# PROIECT.net
KiCad netlist of a schematic drawn in EAGLE
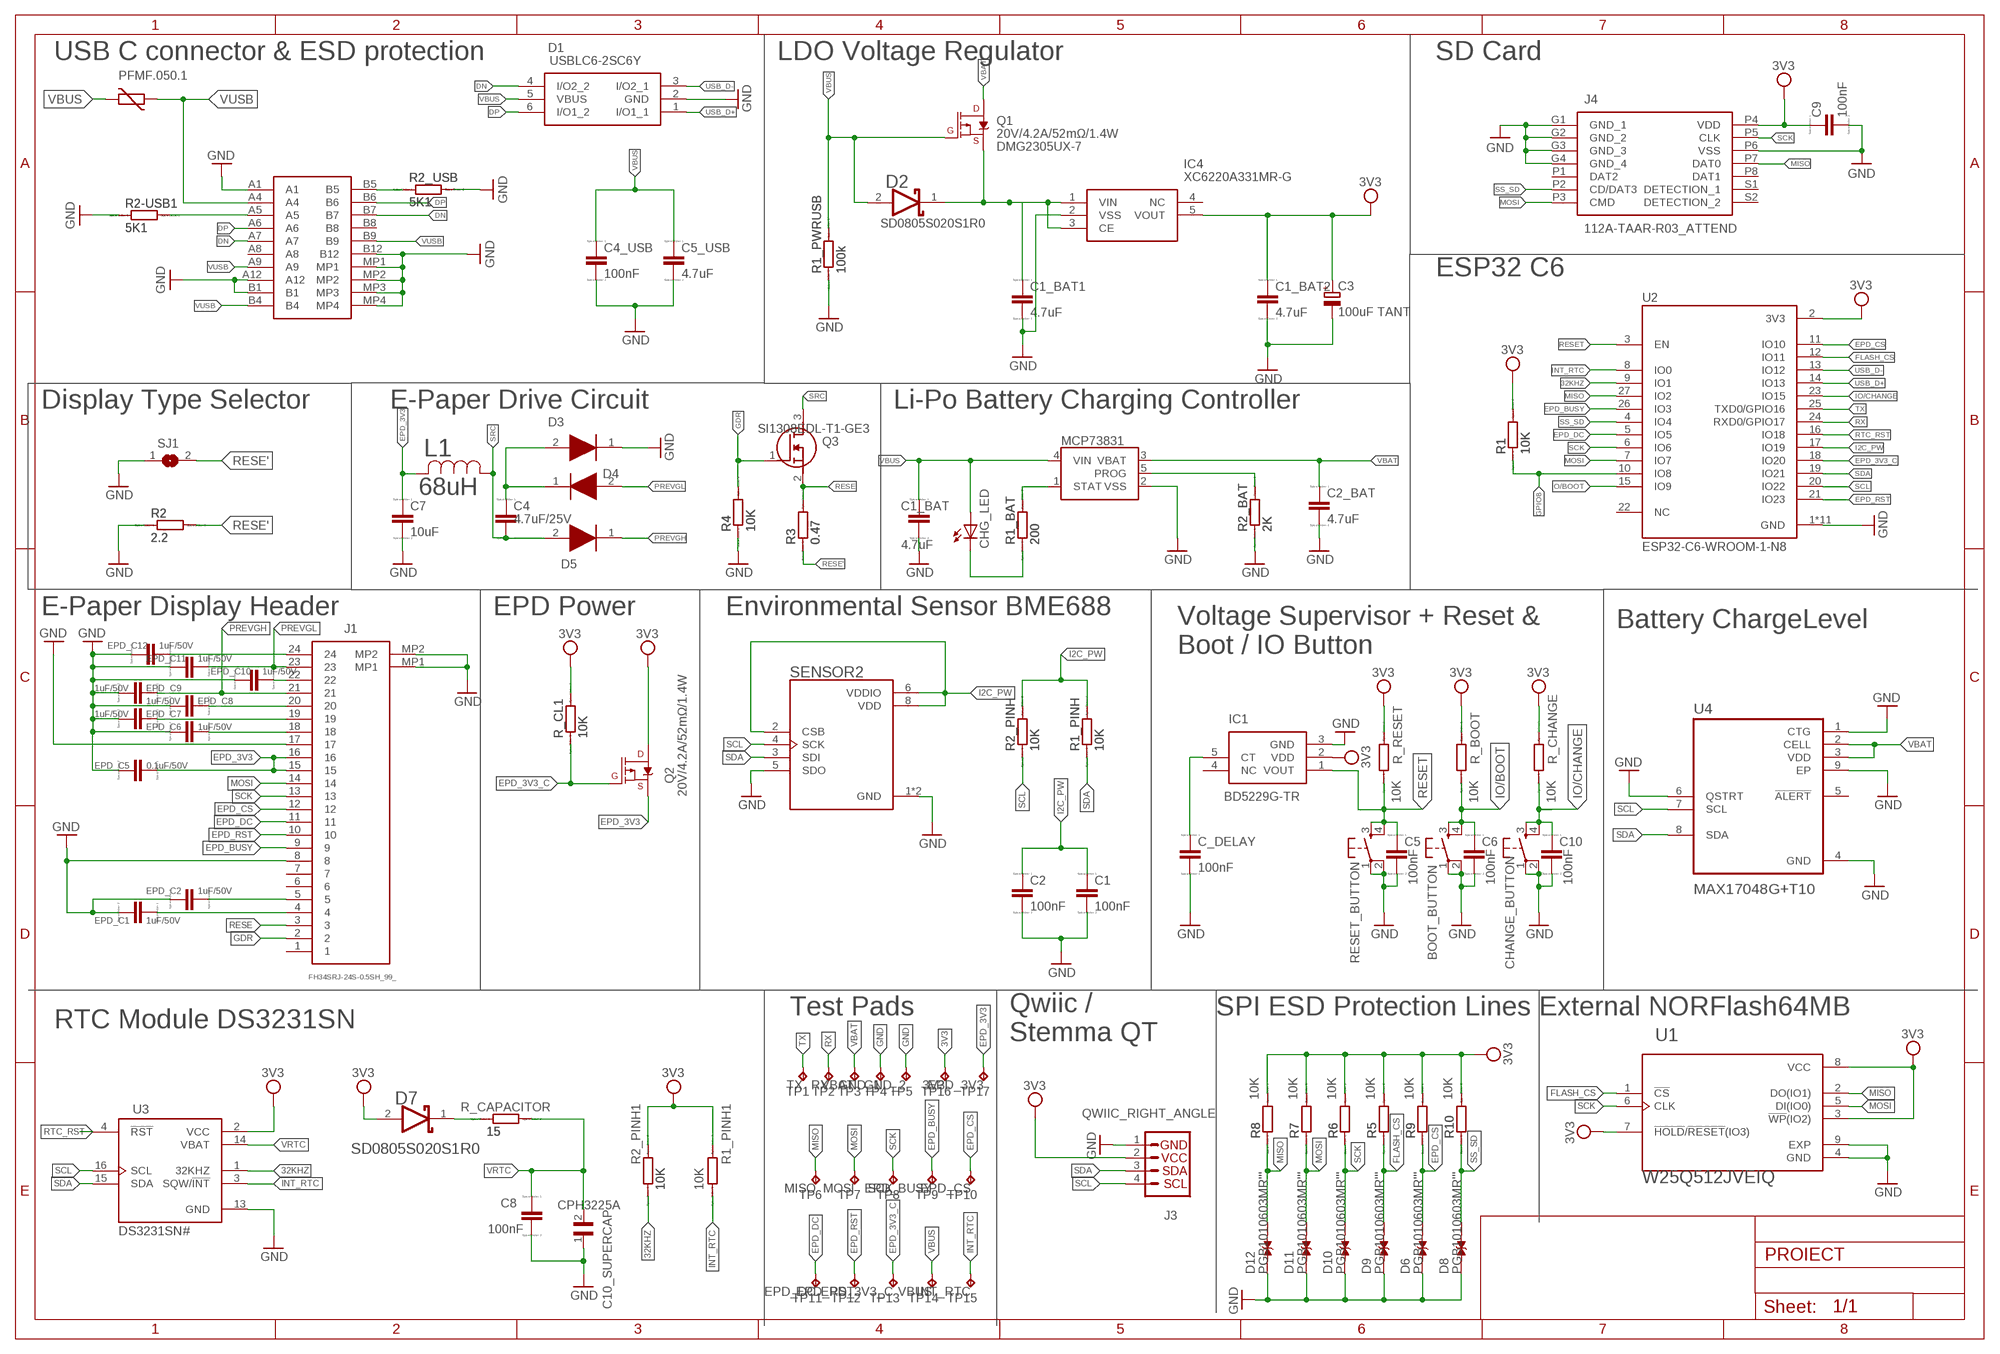
[diagram p0: schematic, sheet 1]

(export (version "E")
  (design (tool "Eeschema 10.0.6"))
  (components
    (comp (ref "BOOT_BUTTON")
      (value "BUTTON_CUSYOMV1")
      (footprint "eagle-import:MYBUTTON")
      (libsource (lib "eagle-import") (part "BUTTON_CUSYOMV1"))
    )
    (comp (ref "C1")
      (value "100nF")
      (footprint "eagle-import:ESP32_WROVER_EAGLE-LTSPICE_C0402")
      (libsource (lib "eagle-import") (part "ESP32_WROVER_EAGLE-LTSPICE_C"))
    )
    (comp (ref "C1_BAT")
      (value "4.7uF")
      (footprint "eagle-import:EAGLE-LTSPICE_C0402")
      (libsource (lib "eagle-import") (part "EAGLE-LTSPICE_CC0402"))
    )
    (comp (ref "C1_BAT1")
      (value "4.7uF")
      (footprint "eagle-import:ESP32_WROVER_EAGLE-LTSPICE_C0402")
      (libsource (lib "eagle-import") (part "ESP32_WROVER_EAGLE-LTSPICE_C"))
    )
    (comp (ref "C1_BAT2")
      (value "4.7uF")
      (footprint "eagle-import:ESP32_WROVER_EAGLE-LTSPICE_C0402")
      (libsource (lib "eagle-import") (part "ESP32_WROVER_EAGLE-LTSPICE_C"))
    )
    (comp (ref "C2")
      (value "100nF")
      (footprint "eagle-import:ESP32_WROVER_EAGLE-LTSPICE_C0402")
      (libsource (lib "eagle-import") (part "ESP32_WROVER_EAGLE-LTSPICE_C"))
    )
    (comp (ref "C2_BAT")
      (value "4.7uF")
      (footprint "eagle-import:EAGLE-LTSPICE_C0402")
      (libsource (lib "eagle-import") (part "EAGLE-LTSPICE_CC0402"))
    )
    (comp (ref "C3")
      (value "100uF TANT")
      (footprint "eagle-import:RCL_CT3528")
      (libsource (lib "eagle-import") (part "RCL_CPOL-EUCT3528"))
    )
    (comp (ref "C4")
      (value "4.7uF/25V")
      (footprint "eagle-import:EAGLE-LTSPICE_C0402")
      (libsource (lib "eagle-import") (part "EAGLE-LTSPICE_CC0402"))
    )
    (comp (ref "C4_USB")
      (value "100nF")
      (footprint "eagle-import:ESP32_WROVER_EAGLE-LTSPICE_C0402")
      (libsource (lib "eagle-import") (part "ESP32_WROVER_EAGLE-LTSPICE_C"))
    )
    (comp (ref "C5")
      (value "100nF")
      (footprint "eagle-import:EAGLE-LTSPICE_C0402")
      (libsource (lib "eagle-import") (part "EAGLE-LTSPICE_CC0402"))
    )
    (comp (ref "C5_USB")
      (value "4.7uF")
      (footprint "eagle-import:ESP32_WROVER_EAGLE-LTSPICE_C0402")
      (libsource (lib "eagle-import") (part "ESP32_WROVER_EAGLE-LTSPICE_C"))
    )
    (comp (ref "C6")
      (value "100nF")
      (footprint "eagle-import:EAGLE-LTSPICE_C0402")
      (libsource (lib "eagle-import") (part "EAGLE-LTSPICE_CC0402"))
    )
    (comp (ref "C7")
      (value "10uF")
      (footprint "eagle-import:EAGLE-LTSPICE_C0402")
      (libsource (lib "eagle-import") (part "EAGLE-LTSPICE_CC0402"))
    )
    (comp (ref "C8")
      (value "100nF")
      (footprint "eagle-import:EAGLE-LTSPICE_C0402")
      (libsource (lib "eagle-import") (part "EAGLE-LTSPICE_CC0402"))
    )
    (comp (ref "C9")
      (value "100nF")
      (footprint "eagle-import:EAGLE-LTSPICE_C0402")
      (libsource (lib "eagle-import") (part "EAGLE-LTSPICE_CC0402"))
    )
    (comp (ref "C10")
      (value "100nF")
      (footprint "eagle-import:EAGLE-LTSPICE_C0402")
      (libsource (lib "eagle-import") (part "EAGLE-LTSPICE_CC0402"))
    )
    (comp (ref "C10_SUPERCAP")
      (value "CPH3225A")
      (footprint "eagle-import:CAPCP3225X100N")
      (fields (field (name "MF") "Seiko Instruments"))
      (libsource (lib "eagle-import") (part "CPH3225A"))
    )
    (comp (ref "CHANGE_BUTTON")
      (value "BUTTON_CUSYOMV1")
      (footprint "eagle-import:MYBUTTON")
      (libsource (lib "eagle-import") (part "BUTTON_CUSYOMV1"))
    )
    (comp (ref "CHG_LED")
      (value "ADAFRUIT_LEDCHIP-LED0603")
      (footprint "eagle-import:ADAFRUIT_CHIP-LED0603")
      (libsource (lib "eagle-import") (part "ADAFRUIT_LEDCHIP-LED0603"))
    )
    (comp (ref "C_DELAY")
      (value "100nF")
      (footprint "eagle-import:EAGLE-LTSPICE_C0402")
      (libsource (lib "eagle-import") (part "EAGLE-LTSPICE_CC0402"))
    )
    (comp (ref "D1")
      (value "USBLC6-2SC6Y")
      (footprint "eagle-import:SOT95P280X145-6N")
      (fields (field (name "MF") "STMicroelectronics"))
      (libsource (lib "eagle-import") (part "USBLC6-2SC6Y"))
    )
    (comp (ref "D2")
      (value "ESP32_WROVER_AVX---SD0805S020S1R0_AVX_SD0805S020S1R0_0_0AVX_SD0805S020S1R0_0_0")
      (footprint "eagle-import:ESP32_WROVER_AVX---SD0805S020S1R0_AVX_SD0805S020S1R0_0")
      (fields
        (field (name "DIGIKEY_PART_NUMBER") "478-7800-1-ND")
        (field (name "MF") "AVX")
        (field (name "MOUSER_PART_NUMBER") "581-SD0805S020S1R0")
      )
      (libsource (lib "eagle-import") (part "ESP32_WROVER_AVX---SD0805S020S1R0_AVX_SD0805S020S1R0_0_0AVX_SD0805S020S1R0_0_0"))
    )
    (comp (ref "D3")
      (value "MBR0530'''")
      (footprint "eagle-import:SOD3716X135N")
      (libsource (lib "eagle-import") (part "MBR0530'''"))
    )
    (comp (ref "D4")
      (value "MBR0530'''")
      (footprint "eagle-import:SOD3716X135N")
      (libsource (lib "eagle-import") (part "MBR0530'''"))
    )
    (comp (ref "D5")
      (value "MBR0530'''")
      (footprint "eagle-import:SOD3716X135N")
      (libsource (lib "eagle-import") (part "MBR0530'''"))
    )
    (comp (ref "D6")
      (value "PGB1010603MR'''")
      (footprint "eagle-import:DIOC1608X36N")
      (libsource (lib "eagle-import") (part "PGB1010603MR'''"))
    )
    (comp (ref "D7")
      (value "ESP32_WROVER_AVX---SD0805S020S1R0_AVX_SD0805S020S1R0_0_0AVX_SD0805S020S1R0_0_0")
      (footprint "eagle-import:ESP32_WROVER_AVX---SD0805S020S1R0_AVX_SD0805S020S1R0_0")
      (fields
        (field (name "DIGIKEY_PART_NUMBER") "478-7800-1-ND")
        (field (name "MF") "AVX")
        (field (name "MOUSER_PART_NUMBER") "581-SD0805S020S1R0")
      )
      (libsource (lib "eagle-import") (part "ESP32_WROVER_AVX---SD0805S020S1R0_AVX_SD0805S020S1R0_0_0AVX_SD0805S020S1R0_0_0"))
    )
    (comp (ref "D8")
      (value "PGB1010603MR'''")
      (footprint "eagle-import:DIOC1608X36N")
      (libsource (lib "eagle-import") (part "PGB1010603MR'''"))
    )
    (comp (ref "D9")
      (value "PGB1010603MR'''")
      (footprint "eagle-import:DIOC1608X36N")
      (libsource (lib "eagle-import") (part "PGB1010603MR'''"))
    )
    (comp (ref "D10")
      (value "PGB1010603MR'''")
      (footprint "eagle-import:DIOC1608X36N")
      (libsource (lib "eagle-import") (part "PGB1010603MR'''"))
    )
    (comp (ref "D11")
      (value "PGB1010603MR'''")
      (footprint "eagle-import:DIOC1608X36N")
      (libsource (lib "eagle-import") (part "PGB1010603MR'''"))
    )
    (comp (ref "D12")
      (value "PGB1010603MR'''")
      (footprint "eagle-import:DIOC1608X36N")
      (libsource (lib "eagle-import") (part "PGB1010603MR'''"))
    )
    (comp (ref "EPD_C1")
      (value "1uF/50V")
      (footprint "eagle-import:EAGLE-LTSPICE_C0402")
      (libsource (lib "eagle-import") (part "EAGLE-LTSPICE_CC0402"))
    )
    (comp (ref "EPD_C2")
      (value "1uF/50V")
      (footprint "eagle-import:EAGLE-LTSPICE_C0402")
      (libsource (lib "eagle-import") (part "EAGLE-LTSPICE_CC0402"))
    )
    (comp (ref "EPD_C5")
      (value "0.1uF/50V")
      (footprint "eagle-import:EAGLE-LTSPICE_C0402")
      (libsource (lib "eagle-import") (part "EAGLE-LTSPICE_CC0402"))
    )
    (comp (ref "EPD_C6")
      (value "1uF/50V")
      (footprint "eagle-import:EAGLE-LTSPICE_C0402")
      (libsource (lib "eagle-import") (part "EAGLE-LTSPICE_CC0402"))
    )
    (comp (ref "EPD_C7")
      (value "1uF/50V")
      (footprint "eagle-import:EAGLE-LTSPICE_C0402")
      (libsource (lib "eagle-import") (part "EAGLE-LTSPICE_CC0402"))
    )
    (comp (ref "EPD_C8")
      (value "1uF/50V")
      (footprint "eagle-import:EAGLE-LTSPICE_C0402")
      (libsource (lib "eagle-import") (part "EAGLE-LTSPICE_CC0402"))
    )
    (comp (ref "EPD_C9")
      (value "1uF/50V")
      (footprint "eagle-import:EAGLE-LTSPICE_C0402")
      (libsource (lib "eagle-import") (part "EAGLE-LTSPICE_CC0402"))
    )
    (comp (ref "EPD_C10")
      (value "1uF/50V")
      (footprint "eagle-import:EAGLE-LTSPICE_C0402")
      (libsource (lib "eagle-import") (part "EAGLE-LTSPICE_CC0402"))
    )
    (comp (ref "EPD_C11")
      (value "1uF/50V")
      (footprint "eagle-import:EAGLE-LTSPICE_C0402")
      (libsource (lib "eagle-import") (part "EAGLE-LTSPICE_CC0402"))
    )
    (comp (ref "EPD_C12")
      (value "1uF/50V")
      (footprint "eagle-import:EAGLE-LTSPICE_C0402")
      (libsource (lib "eagle-import") (part "EAGLE-LTSPICE_CC0402"))
    )
    (comp (ref "IC1")
      (value "BD5229G-TR")
      (footprint "eagle-import:SOT95P280X125-5N")
      (fields (field (name "MOUSER_PART_NUMBER") "755-BD5229G-TR"))
      (libsource (lib "eagle-import") (part "BD5229G-TR"))
    )
    (comp (ref "IC4")
      (value "XC6220A331MR-G")
      (footprint "eagle-import:SOT95P280X120-5N")
      (fields (field (name "MOUSER_PART_NUMBER") "865-XC6220A331MR-G"))
      (libsource (lib "eagle-import") (part "XC6220A331MR-G"))
    )
    (comp (ref "J1")
      (value "FH34SRJ-24S-0.5SH_99_")
      (footprint "eagle-import:FH34SRJ24S05SH99")
      (fields
        (field (name "MANUFACTURER_PART_NUMBER") "FH34SRJ-24S-0.5SH(99)")
        (field (name "MOUSER_PART_NUMBER") "798-FH34SRJ24S05SH99")
      )
      (libsource (lib "eagle-import") (part "FH34SRJ-24S-0.5SH_99_"))
    )
    (comp (ref "J2")
      (value "SAMACSYS_PARTS_USB4110-GF-A")
      (footprint "eagle-import:SAMACSYS_PARTS_USB4110GFA")
      (fields
        (field (name "MANUFACTURER_PART_NUMBER") "USB4110-GF-A")
        (field (name "MOUSER_PART_NUMBER") "640-USB4110-GF-A")
      )
      (libsource (lib "eagle-import") (part "SAMACSYS_PARTS_USB4110-GF-A"))
    )
    (comp (ref "J3")
      (value "QWIIC_RIGHT_ANGLE")
      (footprint "eagle-import:JST04_1MM_RA")
      (libsource (lib "eagle-import") (part "QWIIC_CONNECTORJS-1MM"))
    )
    (comp (ref "J4")
      (value "112A-TAAR-R03_ATTEND")
      (footprint "eagle-import:112ATAARR03ATTEND")
      (fields (field (name "MANUFACTURER_PART_NUMBER") "112A-TAAR-R03 ATTEND"))
      (libsource (lib "eagle-import") (part "112A-TAAR-R03_ATTEND"))
    )
    (comp (ref "L1")
      (value "68uH")
      (footprint "eagle-import:IND_4828-WE-TPC_WRE")
      (fields
        (field (name "MANUFACTURER_PART_NUMBER") "744043680")
        (field (name "COPYRIGHT") "Copyright (C) 2024 Ultra Librarian. All rights reserved.")
      )
      (libsource (lib "eagle-import") (part "744043680IND_4828-WE-TPC_WRE"))
    )
    (comp (ref "MCP73831")
      (value "ESP32_WROVER_SPARKFUN-IC-POWER_MCP73831")
      (footprint "eagle-import:ESP32_WROVER_SPARKFUN-IC-POWER_SOT23-5")
      (libsource (lib "eagle-import") (part "ESP32_WROVER_SPARKFUN-IC-POWER_MCP73831"))
    )
    (comp (ref "PFMF.050.1")
      (value "ESP32C6_VARISTORCN1812")
      (footprint "eagle-import:ESP32C6_VARISTOR_CT_CN1812")
      (libsource (lib "eagle-import") (part "ESP32C6_VARISTORCN1812"))
    )
    (comp (ref "Q1")
      (value "20V/4.2A/52mΩ/1.4W")
      (footprint "eagle-import:ESP32_WROVER_SPARKFUN-DISCRETESEMI_SOT23-3")
      (libsource (lib "eagle-import") (part "ESP32_WROVER_SPARKFUN-DISCRETESEMI_MOSFET_PCH-DMG2305UX-7"))
    )
    (comp (ref "Q2")
      (value "20V/4.2A/52mΩ/1.4W")
      (footprint "eagle-import:ESP32_WROVER_SPARKFUN-DISCRETESEMI_SOT23-3")
      (libsource (lib "eagle-import") (part "ESP32_WROVER_SPARKFUN-DISCRETESEMI_MOSFET_PCH-DMG2305UX-7"))
    )
    (comp (ref "Q3")
      (value "SI1308EDL-T1-GE3")
      (footprint "eagle-import:SOT65P210X110-3N")
      (fields (field (name "MF") "Vishay Siliconix"))
      (libsource (lib "eagle-import") (part "SI1308EDL-T1-GE3"))
    )
    (comp (ref "R1")
      (value "10K")
      (footprint "eagle-import:ESP32_WROVER_EAGLE-LTSPICE_R0402")
      (libsource (lib "eagle-import") (part "ESP32_WROVER_EAGLE-LTSPICE_R"))
    )
    (comp (ref "R1_BAT")
      (value "200")
      (footprint "eagle-import:ESP32_WROVER_EAGLE-LTSPICE_R0402")
      (libsource (lib "eagle-import") (part "ESP32_WROVER_EAGLE-LTSPICE_R"))
    )
    (comp (ref "R1_PINH")
      (value "10K")
      (footprint "eagle-import:ESP32_WROVER_EAGLE-LTSPICE_R0402")
      (libsource (lib "eagle-import") (part "ESP32_WROVER_EAGLE-LTSPICE_R"))
    )
    (comp (ref "R1_PINH1")
      (value "10K")
      (footprint "eagle-import:ESP32_WROVER_EAGLE-LTSPICE_R0402")
      (libsource (lib "eagle-import") (part "ESP32_WROVER_EAGLE-LTSPICE_R"))
    )
    (comp (ref "R1_PWRUSB")
      (value "100k")
      (footprint "eagle-import:ESP32_WROVER_EAGLE-LTSPICE_R0402")
      (libsource (lib "eagle-import") (part "ESP32_WROVER_EAGLE-LTSPICE_R"))
    )
    (comp (ref "R2")
      (value "2.2")
      (footprint "eagle-import:ESP32_WROVER_EAGLE-LTSPICE_R0402")
      (libsource (lib "eagle-import") (part "ESP32_WROVER_EAGLE-LTSPICE_R"))
    )
    (comp (ref "R2-USB1")
      (value "5K1")
      (footprint "eagle-import:ESP32_WROVER_EAGLE-LTSPICE_R0402")
      (libsource (lib "eagle-import") (part "ESP32_WROVER_EAGLE-LTSPICE_R"))
    )
    (comp (ref "R2_BAT")
      (value "2K")
      (footprint "eagle-import:ESP32_WROVER_EAGLE-LTSPICE_R0402")
      (libsource (lib "eagle-import") (part "ESP32_WROVER_EAGLE-LTSPICE_R"))
    )
    (comp (ref "R2_PINH")
      (value "10K")
      (footprint "eagle-import:ESP32_WROVER_EAGLE-LTSPICE_R0402")
      (libsource (lib "eagle-import") (part "ESP32_WROVER_EAGLE-LTSPICE_R"))
    )
    (comp (ref "R2_PINH1")
      (value "10K")
      (footprint "eagle-import:ESP32_WROVER_EAGLE-LTSPICE_R0402")
      (libsource (lib "eagle-import") (part "ESP32_WROVER_EAGLE-LTSPICE_R"))
    )
    (comp (ref "R2_USB")
      (value "5K1")
      (footprint "eagle-import:ESP32_WROVER_EAGLE-LTSPICE_R0402")
      (libsource (lib "eagle-import") (part "ESP32_WROVER_EAGLE-LTSPICE_R"))
    )
    (comp (ref "R3")
      (value "0.47")
      (footprint "eagle-import:ESP32_WROVER_EAGLE-LTSPICE_R0402")
      (libsource (lib "eagle-import") (part "ESP32_WROVER_EAGLE-LTSPICE_R"))
    )
    (comp (ref "R4")
      (value "10K")
      (footprint "eagle-import:ESP32_WROVER_EAGLE-LTSPICE_R0402")
      (libsource (lib "eagle-import") (part "ESP32_WROVER_EAGLE-LTSPICE_R"))
    )
    (comp (ref "R5")
      (value "10K")
      (footprint "eagle-import:ESP32_WROVER_EAGLE-LTSPICE_R0402")
      (libsource (lib "eagle-import") (part "ESP32_WROVER_EAGLE-LTSPICE_R"))
    )
    (comp (ref "R6")
      (value "10K")
      (footprint "eagle-import:ESP32_WROVER_EAGLE-LTSPICE_R0402")
      (libsource (lib "eagle-import") (part "ESP32_WROVER_EAGLE-LTSPICE_R"))
    )
    (comp (ref "R7")
      (value "10K")
      (footprint "eagle-import:ESP32_WROVER_EAGLE-LTSPICE_R0402")
      (libsource (lib "eagle-import") (part "ESP32_WROVER_EAGLE-LTSPICE_R"))
    )
    (comp (ref "R8")
      (value "10K")
      (footprint "eagle-import:ESP32_WROVER_EAGLE-LTSPICE_R0402")
      (libsource (lib "eagle-import") (part "ESP32_WROVER_EAGLE-LTSPICE_R"))
    )
    (comp (ref "R9")
      (value "10K")
      (footprint "eagle-import:ESP32_WROVER_EAGLE-LTSPICE_R0402")
      (libsource (lib "eagle-import") (part "ESP32_WROVER_EAGLE-LTSPICE_R"))
    )
    (comp (ref "R10")
      (value "10K")
      (footprint "eagle-import:ESP32_WROVER_EAGLE-LTSPICE_R0402")
      (libsource (lib "eagle-import") (part "ESP32_WROVER_EAGLE-LTSPICE_R"))
    )
    (comp (ref "RESET_BUTTON")
      (value "BUTTON_CUSYOMV1")
      (footprint "eagle-import:MYBUTTON")
      (libsource (lib "eagle-import") (part "BUTTON_CUSYOMV1"))
    )
    (comp (ref "R_BOOT")
      (value "10K")
      (footprint "eagle-import:ESP32_WROVER_EAGLE-LTSPICE_R0402")
      (libsource (lib "eagle-import") (part "ESP32_WROVER_EAGLE-LTSPICE_R"))
    )
    (comp (ref "R_CAPACITOR")
      (value "15")
      (footprint "eagle-import:ESP32_WROVER_EAGLE-LTSPICE_R0402")
      (libsource (lib "eagle-import") (part "ESP32_WROVER_EAGLE-LTSPICE_R"))
    )
    (comp (ref "R_CHANGE")
      (value "10K")
      (footprint "eagle-import:ESP32_WROVER_EAGLE-LTSPICE_R0402")
      (libsource (lib "eagle-import") (part "ESP32_WROVER_EAGLE-LTSPICE_R"))
    )
    (comp (ref "R_CL1")
      (value "10K")
      (footprint "eagle-import:ESP32_WROVER_EAGLE-LTSPICE_R0402")
      (libsource (lib "eagle-import") (part "ESP32_WROVER_EAGLE-LTSPICE_R"))
    )
    (comp (ref "R_RESET")
      (value "10K")
      (footprint "eagle-import:ESP32_WROVER_EAGLE-LTSPICE_R0402")
      (libsource (lib "eagle-import") (part "ESP32_WROVER_EAGLE-LTSPICE_R"))
    )
    (comp (ref "SENSOR2")
      (value "ESP32_WROVER_BME680_BME680")
      (footprint "eagle-import:ESP32_WROVER_BME680_PSON80P300X300X100-8N")
      (fields (field (name "MF") "Bosch Sensortec") (field (name "MP") "BME680"))
      (libsource (lib "eagle-import") (part "ESP32_WROVER_BME680_BME680"))
    )
    (comp (ref "SJ1") (value "SJ") (footprint "eagle-import:SJ") (libsource (lib "eagle-import") (part "SJ")))
    (comp (ref "TP1")
      (value "TPTP20R")
      (footprint "eagle-import:TP20R")
      (fields (field (name "3D_TX") "TX"))
      (libsource (lib "eagle-import") (part "TPTP20R"))
    )
    (comp (ref "TP2")
      (value "TPTP20R")
      (footprint "eagle-import:TP20R")
      (fields (field (name "3D_RX") "RX"))
      (libsource (lib "eagle-import") (part "TPTP20R"))
    )
    (comp (ref "TP3")
      (value "TPTP20R")
      (footprint "eagle-import:TP20R")
      (fields (field (name "3D_VBAT") "VBAT"))
      (libsource (lib "eagle-import") (part "TPTP20R"))
    )
    (comp (ref "TP4")
      (value "TPTP20R")
      (footprint "eagle-import:TP20R")
      (fields (field (name "3D_GND") "GND_1"))
      (libsource (lib "eagle-import") (part "TPTP20R"))
    )
    (comp (ref "TP5")
      (value "TPTP20R")
      (footprint "eagle-import:TP20R")
      (fields (field (name "3D_GND2") "GND_2"))
      (libsource (lib "eagle-import") (part "TPTP20R"))
    )
    (comp (ref "TP6")
      (value "TPTP20R")
      (footprint "eagle-import:TP20R")
      (fields (field (name "3D_MISO") "MISO"))
      (libsource (lib "eagle-import") (part "TPTP20R"))
    )
    (comp (ref "TP7")
      (value "TPTP20R")
      (footprint "eagle-import:TP20R")
      (fields (field (name "3D_MOSI") "MOSI"))
      (libsource (lib "eagle-import") (part "TPTP20R"))
    )
    (comp (ref "TP8")
      (value "TPTP20R")
      (footprint "eagle-import:TP20R")
      (fields (field (name "3D_SCK") "SCK"))
      (libsource (lib "eagle-import") (part "TPTP20R"))
    )
    (comp (ref "TP9")
      (value "TPTP20R")
      (footprint "eagle-import:TP20R")
      (fields (field (name "3D_EPD_BUSY") "EPD_BUSY"))
      (libsource (lib "eagle-import") (part "TPTP20R"))
    )
    (comp (ref "TP10")
      (value "TPTP20R")
      (footprint "eagle-import:TP20R")
      (fields (field (name "3D_EPD_CS") "EPD_CS"))
      (libsource (lib "eagle-import") (part "TPTP20R"))
    )
    (comp (ref "TP11")
      (value "TPTP20R")
      (footprint "eagle-import:TP20R")
      (fields (field (name "3D_EPD_DC") "EPD_DC"))
      (libsource (lib "eagle-import") (part "TPTP20R"))
    )
    (comp (ref "TP12")
      (value "TPTP20R")
      (footprint "eagle-import:TP20R")
      (fields (field (name "3D_EPD_RST") "EPD_RST"))
      (libsource (lib "eagle-import") (part "TPTP20R"))
    )
    (comp (ref "TP13")
      (value "TPTP20R")
      (footprint "eagle-import:TP20R")
      (fields (field (name "3D_EPD_3V3_C") "EPD_3V3_C"))
      (libsource (lib "eagle-import") (part "TPTP20R"))
    )
    (comp (ref "TP14")
      (value "TPTP20R")
      (footprint "eagle-import:TP20R")
      (fields (field (name "3D_VBUS") "VBUS"))
      (libsource (lib "eagle-import") (part "TPTP20R"))
    )
    (comp (ref "TP15")
      (value "TPTP20R")
      (footprint "eagle-import:TP20R")
      (fields (field (name "3D_INT_RTC") "INT_RTC"))
      (libsource (lib "eagle-import") (part "TPTP20R"))
    )
    (comp (ref "TP16")
      (value "TPTP20R")
      (footprint "eagle-import:TP20R")
      (fields (field (name "3D_3V3") "3V3"))
      (libsource (lib "eagle-import") (part "TPTP20R"))
    )
    (comp (ref "TP17")
      (value "TPTP20R")
      (footprint "eagle-import:TP20R")
      (fields (field (name "3D_EPD_3V3") "EPD_3V3"))
      (libsource (lib "eagle-import") (part "TPTP20R"))
    )
    (comp (ref "U1")
      (value "W25Q512JVEIQ")
      (footprint "eagle-import:SON127P600X800X80-9N")
      (fields (field (name "MF") "Winbond Electronics"))
      (libsource (lib "eagle-import") (part "W25Q512JVEIQ"))
    )
    (comp (ref "U2")
      (value "ESP32-C6-WROOM-1-N8")
      (footprint "eagle-import:XCVR_ESP32-C6-WROOM-1-N8")
      (fields (field (name "MF") "Espressif Systems"))
      (libsource (lib "eagle-import") (part "ESP32-C6-WROOM-1-N8"))
    )
    (comp (ref "U3")
      (value "DS3231SN#")
      (footprint "eagle-import:SOIC127P1032X265-16N")
      (fields (field (name "MF") "Analog Devices"))
      (libsource (lib "eagle-import") (part "DS3231SN#"))
    )
    (comp (ref "U4")
      (value "MAX17048G+T10")
      (footprint "eagle-import:SON50P200X200X80-9N")
      (fields (field (name "MF") "Analog Devices"))
      (libsource (lib "eagle-import") (part "MAX17048G+T10"))
    )
  )
  (nets
    (net (code "1") (name "3V3") (class "Default")
      (node (ref "C1_BAT2") (pin "1") (pinfunction "1_1") (pintype "passive"))
      (node (ref "C3") (pin "+") (pinfunction "+_+") (pintype "passive"))
      (node (ref "C9") (pin "1") (pinfunction "1_1") (pintype "passive"))
      (node (ref "D7") (pin "2") (pinfunction "ANODE_2") (pintype "bidirectional"))
      (node (ref "IC1") (pin "2") (pinfunction "VDD_2") (pintype "bidirectional"))
      (node (ref "IC4") (pin "5") (pinfunction "VOUT_5") (pintype "bidirectional"))
      (node (ref "J3") (pin "2") (pinfunction "2_2") (pintype "power_in"))
      (node (ref "J4") (pin "P4") (pinfunction "VDD_P4") (pintype "bidirectional"))
      (node (ref "Q2") (pin "3") (pinfunction "D_3") (pintype "bidirectional"))
      (node (ref "R1") (pin "2") (pinfunction "2_2") (pintype "passive"))
      (node (ref "R10") (pin "2") (pinfunction "2_2") (pintype "passive"))
      (node (ref "R1_PINH1") (pin "2") (pinfunction "2_2") (pintype "passive"))
      (node (ref "R2_PINH1") (pin "2") (pinfunction "2_2") (pintype "passive"))
      (node (ref "R5") (pin "2") (pinfunction "2_2") (pintype "passive"))
      (node (ref "R6") (pin "2") (pinfunction "2_2") (pintype "passive"))
      (node (ref "R7") (pin "2") (pinfunction "2_2") (pintype "passive"))
      (node (ref "R8") (pin "2") (pinfunction "2_2") (pintype "passive"))
      (node (ref "R9") (pin "2") (pinfunction "2_2") (pintype "passive"))
      (node (ref "R_BOOT") (pin "2") (pinfunction "2_2") (pintype "passive"))
      (node (ref "R_CHANGE") (pin "2") (pinfunction "2_2") (pintype "passive"))
      (node (ref "R_CL1") (pin "2") (pinfunction "2_2") (pintype "passive"))
      (node (ref "R_RESET") (pin "2") (pinfunction "2_2") (pintype "passive"))
      (node (ref "TP16") (pin "TP") (pinfunction "TP_TP") (pintype "input"))
      (node (ref "U1") (pin "3") (pinfunction "~{WP}(IO2)_3") (pintype "bidirectional"))
      (node (ref "U1") (pin "7") (pinfunction "~{HOLD}/~{RESET}(IO3)_7") (pintype "bidirectional"))
      (node (ref "U1") (pin "8") (pinfunction "VCC_8") (pintype "power_in"))
      (node (ref "U2") (pin "2") (pinfunction "3V3_2") (pintype "power_in"))
      (node (ref "U3") (pin "2") (pinfunction "VCC_2") (pintype "power_in"))
    )
    (net (code "2") (name "32KHZ") (class "Default")
      (node (ref "R2_PINH1") (pin "1") (pinfunction "1_1") (pintype "passive"))
      (node (ref "U2") (pin "9") (pinfunction "IO1_9") (pintype "bidirectional"))
      (node (ref "U3") (pin "1") (pinfunction "32KHZ_1") (pintype "output"))
    )
    (net (code "3") (name "DN") (class "Default")
      (node (ref "D1") (pin "4") (pinfunction "I/O2_2_4") (pintype "bidirectional"))
      (node (ref "J2") (pin "A7") (pinfunction "A7_A7") (pintype "bidirectional"))
      (node (ref "J2") (pin "B7") (pinfunction "B7_B7") (pintype "bidirectional"))
    )
    (net (code "4") (name "DP") (class "Default")
      (node (ref "D1") (pin "6") (pinfunction "I/O1_2_6") (pintype "bidirectional"))
      (node (ref "J2") (pin "A6") (pinfunction "A6_A6") (pintype "bidirectional"))
      (node (ref "J2") (pin "B6") (pinfunction "B6_B6") (pintype "bidirectional"))
    )
    (net (code "5") (name "EPD_3V3") (class "Default")
      (node (ref "C7") (pin "1") (pinfunction "1_1") (pintype "passive"))
      (node (ref "EPD_C5") (pin "1") (pinfunction "1_1") (pintype "passive"))
      (node (ref "J1") (pin "15") (pinfunction "15_15") (pintype "bidirectional"))
      (node (ref "J1") (pin "16") (pinfunction "16_16") (pintype "bidirectional"))
      (node (ref "L1") (pin "2") (pinfunction "2_2") (pintype "passive"))
      (node (ref "Q2") (pin "2") (pinfunction "S_2") (pintype "bidirectional"))
      (node (ref "TP17") (pin "TP") (pinfunction "TP_TP") (pintype "input"))
    )
    (net (code "6") (name "EPD_3V3_C") (class "Default")
      (node (ref "Q2") (pin "1") (pinfunction "G_1") (pintype "bidirectional"))
      (node (ref "R_CL1") (pin "1") (pinfunction "1_1") (pintype "passive"))
      (node (ref "TP13") (pin "TP") (pinfunction "TP_TP") (pintype "input"))
      (node (ref "U2") (pin "18") (pinfunction "IO20_18") (pintype "bidirectional"))
    )
    (net (code "7") (name "EPD_BUSY") (class "Default")
      (node (ref "J1") (pin "9") (pinfunction "9_9") (pintype "bidirectional"))
      (node (ref "TP9") (pin "TP") (pinfunction "TP_TP") (pintype "input"))
      (node (ref "U2") (pin "26") (pinfunction "IO3_26") (pintype "bidirectional"))
    )
    (net (code "8") (name "EPD_CS") (class "Default")
      (node (ref "D6") (pin "2") (pinfunction "2_2") (pintype "passive"))
      (node (ref "J1") (pin "12") (pinfunction "12_12") (pintype "bidirectional"))
      (node (ref "R9") (pin "1") (pinfunction "1_1") (pintype "passive"))
      (node (ref "TP10") (pin "TP") (pinfunction "TP_TP") (pintype "input"))
      (node (ref "U2") (pin "11") (pinfunction "IO10_11") (pintype "bidirectional"))
    )
    (net (code "9") (name "EPD_DC") (class "Default")
      (node (ref "J1") (pin "11") (pinfunction "11_11") (pintype "bidirectional"))
      (node (ref "TP11") (pin "TP") (pinfunction "TP_TP") (pintype "input"))
      (node (ref "U2") (pin "5") (pinfunction "IO5_5") (pintype "bidirectional"))
    )
    (net (code "10") (name "EPD_RST") (class "Default")
      (node (ref "J1") (pin "10") (pinfunction "10_10") (pintype "bidirectional"))
      (node (ref "TP12") (pin "TP") (pinfunction "TP_TP") (pintype "input"))
      (node (ref "U2") (pin "21") (pinfunction "IO23_21") (pintype "bidirectional"))
    )
    (net (code "11") (name "FLASH_CS") (class "Default")
      (node (ref "D9") (pin "2") (pinfunction "2_2") (pintype "passive"))
      (node (ref "R5") (pin "1") (pinfunction "1_1") (pintype "passive"))
      (node (ref "U1") (pin "1") (pinfunction "~{CS}_1") (pintype "input"))
      (node (ref "U2") (pin "12") (pinfunction "IO11_12") (pintype "bidirectional"))
    )
    (net (code "12") (name "GDR") (class "Default")
      (node (ref "J1") (pin "2") (pinfunction "2_2") (pintype "bidirectional"))
      (node (ref "Q3") (pin "1") (pinfunction "G_1") (pintype "bidirectional"))
      (node (ref "R4") (pin "2") (pinfunction "2_2") (pintype "passive"))
    )
    (net (code "13") (name "GND") (class "Default")
      (node (ref "BOOT_BUTTON") (pin "1") (pinfunction "1_1") (pintype "passive"))
      (node (ref "BOOT_BUTTON") (pin "2") (pinfunction "2_2") (pintype "passive"))
      (node (ref "C1") (pin "2") (pinfunction "2_2") (pintype "passive"))
      (node (ref "C10") (pin "2") (pinfunction "2_2") (pintype "passive"))
      (node (ref "C10_SUPERCAP") (pin "1") (pinfunction "1_1") (pintype "passive"))
      (node (ref "C1_BAT") (pin "2") (pinfunction "2_2") (pintype "passive"))
      (node (ref "C1_BAT1") (pin "2") (pinfunction "2_2") (pintype "passive"))
      (node (ref "C1_BAT2") (pin "2") (pinfunction "2_2") (pintype "passive"))
      (node (ref "C2") (pin "2") (pinfunction "2_2") (pintype "passive"))
      (node (ref "C2_BAT") (pin "2") (pinfunction "2_2") (pintype "passive"))
      (node (ref "C3") (pin "-") (pinfunction "-_-") (pintype "passive"))
      (node (ref "C4_USB") (pin "2") (pinfunction "2_2") (pintype "passive"))
      (node (ref "C5") (pin "2") (pinfunction "2_2") (pintype "passive"))
      (node (ref "C5_USB") (pin "2") (pinfunction "2_2") (pintype "passive"))
      (node (ref "C6") (pin "2") (pinfunction "2_2") (pintype "passive"))
      (node (ref "C7") (pin "2") (pinfunction "2_2") (pintype "passive"))
      (node (ref "C8") (pin "2") (pinfunction "2_2") (pintype "passive"))
      (node (ref "C9") (pin "2") (pinfunction "2_2") (pintype "passive"))
      (node (ref "CHANGE_BUTTON") (pin "1") (pinfunction "1_1") (pintype "passive"))
      (node (ref "CHANGE_BUTTON") (pin "2") (pinfunction "2_2") (pintype "passive"))
      (node (ref "C_DELAY") (pin "2") (pinfunction "2_2") (pintype "passive"))
      (node (ref "D1") (pin "2") (pinfunction "GND_2") (pintype "bidirectional"))
      (node (ref "D10") (pin "1") (pinfunction "1_1") (pintype "passive"))
      (node (ref "D11") (pin "1") (pinfunction "1_1") (pintype "passive"))
      (node (ref "D12") (pin "1") (pinfunction "1_1") (pintype "passive"))
      (node (ref "D3") (pin "1") (pinfunction "K_1") (pintype "bidirectional"))
      (node (ref "D6") (pin "1") (pinfunction "1_1") (pintype "passive"))
      (node (ref "D8") (pin "1") (pinfunction "1_1") (pintype "passive"))
      (node (ref "D9") (pin "1") (pinfunction "1_1") (pintype "passive"))
      (node (ref "EPD_C1") (pin "2") (pinfunction "2_2") (pintype "passive"))
      (node (ref "EPD_C10") (pin "2") (pinfunction "2_2") (pintype "passive"))
      (node (ref "EPD_C11") (pin "2") (pinfunction "2_2") (pintype "passive"))
      (node (ref "EPD_C12") (pin "2") (pinfunction "2_2") (pintype "passive"))
      (node (ref "EPD_C2") (pin "2") (pinfunction "2_2") (pintype "passive"))
      (node (ref "EPD_C5") (pin "2") (pinfunction "2_2") (pintype "passive"))
      (node (ref "EPD_C6") (pin "2") (pinfunction "2_2") (pintype "passive"))
      (node (ref "EPD_C7") (pin "2") (pinfunction "2_2") (pintype "passive"))
      (node (ref "EPD_C8") (pin "2") (pinfunction "2_2") (pintype "passive"))
      (node (ref "EPD_C9") (pin "2") (pinfunction "2_2") (pintype "passive"))
      (node (ref "IC1") (pin "3") (pinfunction "GND_3") (pintype "bidirectional"))
      (node (ref "IC4") (pin "2") (pinfunction "VSS_2") (pintype "bidirectional"))
      (node (ref "J1") (pin "17") (pinfunction "17_17") (pintype "bidirectional"))
      (node (ref "J1") (pin "8") (pinfunction "8_8") (pintype "bidirectional"))
      (node (ref "J1") (pin "MP1") (pinfunction "MP1_MP1") (pintype "bidirectional"))
      (node (ref "J1") (pin "MP2") (pinfunction "MP2_MP2") (pintype "bidirectional"))
      (node (ref "J2") (pin "A1") (pinfunction "A1_A1") (pintype "bidirectional"))
      (node (ref "J2") (pin "A12") (pinfunction "A12_A12") (pintype "bidirectional"))
      (node (ref "J2") (pin "B1") (pinfunction "B1_B1") (pintype "bidirectional"))
      (node (ref "J2") (pin "B12") (pinfunction "B12_B12") (pintype "bidirectional"))
      (node (ref "J2") (pin "MP1") (pinfunction "MP1_MP1") (pintype "bidirectional"))
      (node (ref "J2") (pin "MP2") (pinfunction "MP2_MP2") (pintype "bidirectional"))
      (node (ref "J2") (pin "MP3") (pinfunction "MP3_MP3") (pintype "bidirectional"))
      (node (ref "J2") (pin "MP4") (pinfunction "MP4_MP4") (pintype "bidirectional"))
      (node (ref "J3") (pin "1") (pinfunction "1_1") (pintype "power_in"))
      (node (ref "J4") (pin "G1") (pinfunction "GND_1_G1") (pintype "bidirectional"))
      (node (ref "J4") (pin "G2") (pinfunction "GND_2_G2") (pintype "bidirectional"))
      (node (ref "J4") (pin "G3") (pinfunction "GND_3_G3") (pintype "bidirectional"))
      (node (ref "J4") (pin "G4") (pinfunction "GND_4_G4") (pintype "bidirectional"))
      (node (ref "J4") (pin "P6") (pinfunction "VSS_P6") (pintype "bidirectional"))
      (node (ref "MCP73831") (pin "2") (pinfunction "VSS_2") (pintype "power_in"))
      (node (ref "R1_PWRUSB") (pin "1") (pinfunction "1_1") (pintype "passive"))
      (node (ref "R2") (pin "1") (pinfunction "1_1") (pintype "passive"))
      (node (ref "R2-USB1") (pin "1") (pinfunction "1_1") (pintype "passive"))
      (node (ref "R2_BAT") (pin "1") (pinfunction "1_1") (pintype "passive"))
      (node (ref "R2_USB") (pin "2") (pinfunction "2_2") (pintype "passive"))
      (node (ref "R4") (pin "1") (pinfunction "1_1") (pintype "passive"))
      (node (ref "RESET_BUTTON") (pin "1") (pinfunction "1_1") (pintype "passive"))
      (node (ref "RESET_BUTTON") (pin "2") (pinfunction "2_2") (pintype "passive"))
      (node (ref "SENSOR2") (pin "1") (pinfunction "GND_1") (pintype "power_in"))
      (node (ref "SENSOR2") (pin "5") (pinfunction "SDO_5") (pintype "bidirectional"))
      (node (ref "SENSOR2") (pin "7") (pinfunction "GND_7") (pintype "power_in"))
      (node (ref "SJ1") (pin "1") (pinfunction "1_1") (pintype "passive"))
      (node (ref "TP4") (pin "TP") (pinfunction "TP_TP") (pintype "input"))
      (node (ref "TP5") (pin "TP") (pinfunction "TP_TP") (pintype "input"))
      (node (ref "U1") (pin "4") (pinfunction "GND_4") (pintype "power_in"))
      (node (ref "U1") (pin "9") (pinfunction "EXP_9") (pintype "passive"))
      (node (ref "U2") (pin "1") (pinfunction "GND_1") (pintype "power_in"))
      (node (ref "U2") (pin "28") (pinfunction "GND_28") (pintype "power_in"))
      (node (ref "U2") (pin "29_1") (pinfunction "GND_29_1") (pintype "power_in"))
      (node (ref "U2") (pin "29_2") (pinfunction "GND_29_2") (pintype "power_in"))
      (node (ref "U2") (pin "29_3") (pinfunction "GND_29_3") (pintype "power_in"))
      (node (ref "U2") (pin "29_4") (pinfunction "GND_29_4") (pintype "power_in"))
      (node (ref "U2") (pin "29_5") (pinfunction "GND_29_5") (pintype "power_in"))
      (node (ref "U2") (pin "29_6") (pinfunction "GND_29_6") (pintype "power_in"))
      (node (ref "U2") (pin "29_7") (pinfunction "GND_29_7") (pintype "power_in"))
      (node (ref "U2") (pin "29_8") (pinfunction "GND_29_8") (pintype "power_in"))
      (node (ref "U2") (pin "29_9") (pinfunction "GND_29_9") (pintype "power_in"))
      (node (ref "U3") (pin "13") (pinfunction "GND_13") (pintype "power_in"))
      (node (ref "U4") (pin "1") (pinfunction "CTG_1") (pintype "power_in"))
      (node (ref "U4") (pin "4") (pinfunction "GND_4") (pintype "power_in"))
      (node (ref "U4") (pin "6") (pinfunction "QSTRT_6") (pintype "input"))
      (node (ref "U4") (pin "9") (pinfunction "EP_9") (pintype "power_in"))
    )
    (net (code "14") (name "GPIO8") (class "Default")
      (node (ref "R1") (pin "1") (pinfunction "1_1") (pintype "passive"))
      (node (ref "U2") (pin "10") (pinfunction "IO8_10") (pintype "bidirectional"))
    )
    (net (code "15") (name "I2C_PW") (class "Default")
      (node (ref "C1") (pin "1") (pinfunction "1_1") (pintype "passive"))
      (node (ref "C2") (pin "1") (pinfunction "1_1") (pintype "passive"))
      (node (ref "R1_PINH") (pin "2") (pinfunction "2_2") (pintype "passive"))
      (node (ref "R2_PINH") (pin "2") (pinfunction "2_2") (pintype "passive"))
      (node (ref "SENSOR2") (pin "2") (pinfunction "CSB_2") (pintype "input"))
      (node (ref "SENSOR2") (pin "6") (pinfunction "VDDIO_6") (pintype "power_in"))
      (node (ref "SENSOR2") (pin "8") (pinfunction "VDD_8") (pintype "power_in"))
      (node (ref "U2") (pin "17") (pinfunction "IO19_17") (pintype "bidirectional"))
    )
    (net (code "16") (name "INT_RTC") (class "Default")
      (node (ref "R1_PINH1") (pin "1") (pinfunction "1_1") (pintype "passive"))
      (node (ref "TP15") (pin "TP") (pinfunction "TP_TP") (pintype "input"))
      (node (ref "U2") (pin "8") (pinfunction "IO0_8") (pintype "bidirectional"))
      (node (ref "U3") (pin "3") (pinfunction "SQW/~{INT}_3") (pintype "output"))
    )
    (net (code "17") (name "IO{slash}BOOT") (class "Default")
      (node (ref "BOOT_BUTTON") (pin "3") (pinfunction "3_3") (pintype "passive"))
      (node (ref "BOOT_BUTTON") (pin "4") (pinfunction "4_4") (pintype "passive"))
      (node (ref "C6") (pin "1") (pinfunction "1_1") (pintype "passive"))
      (node (ref "R_BOOT") (pin "1") (pinfunction "1_1") (pintype "passive"))
      (node (ref "U2") (pin "15") (pinfunction "IO9_15") (pintype "bidirectional"))
    )
    (net (code "18") (name "IO{slash}CHANGE") (class "Default")
      (node (ref "C10") (pin "1") (pinfunction "1_1") (pintype "passive"))
      (node (ref "CHANGE_BUTTON") (pin "3") (pinfunction "3_3") (pintype "passive"))
      (node (ref "CHANGE_BUTTON") (pin "4") (pinfunction "4_4") (pintype "passive"))
      (node (ref "R_CHANGE") (pin "1") (pinfunction "1_1") (pintype "passive"))
      (node (ref "U2") (pin "23") (pinfunction "IO15_23") (pintype "bidirectional"))
    )
    (net (code "19") (name "MISO") (class "Default")
      (node (ref "D12") (pin "2") (pinfunction "2_2") (pintype "passive"))
      (node (ref "J4") (pin "P7") (pinfunction "DAT0_P7") (pintype "bidirectional"))
      (node (ref "R8") (pin "1") (pinfunction "1_1") (pintype "passive"))
      (node (ref "TP6") (pin "TP") (pinfunction "TP_TP") (pintype "input"))
      (node (ref "U1") (pin "2") (pinfunction "DO(IO1)_2") (pintype "bidirectional"))
      (node (ref "U2") (pin "27") (pinfunction "IO2_27") (pintype "bidirectional"))
    )
    (net (code "20") (name "MOSI") (class "Default")
      (node (ref "D11") (pin "2") (pinfunction "2_2") (pintype "passive"))
      (node (ref "J1") (pin "14") (pinfunction "14_14") (pintype "bidirectional"))
      (node (ref "J4") (pin "P3") (pinfunction "CMD_P3") (pintype "bidirectional"))
      (node (ref "R7") (pin "1") (pinfunction "1_1") (pintype "passive"))
      (node (ref "TP7") (pin "TP") (pinfunction "TP_TP") (pintype "input"))
      (node (ref "U1") (pin "5") (pinfunction "DI(IO0)_5") (pintype "bidirectional"))
      (node (ref "U2") (pin "7") (pinfunction "IO7_7") (pintype "bidirectional"))
    )
    (net (code "21") (name "Net-(CHG_LED-PadC)") (class "Default")
      (node (ref "CHG_LED") (pin "C") (pinfunction "C_C") (pintype "passive"))
      (node (ref "R1_BAT") (pin "1") (pinfunction "1_1") (pintype "passive"))
    )
    (net (code "22") (name "Net-(D2-CATHODE)") (class "Default")
      (node (ref "C1_BAT1") (pin "1") (pinfunction "1_1") (pintype "passive"))
      (node (ref "D2") (pin "1") (pinfunction "CATHODE_1") (pintype "bidirectional"))
      (node (ref "IC4") (pin "1") (pinfunction "VIN_1") (pintype "bidirectional"))
      (node (ref "IC4") (pin "3") (pinfunction "CE_3") (pintype "bidirectional"))
      (node (ref "Q1") (pin "2") (pinfunction "S_2") (pintype "bidirectional"))
    )
    (net (code "23") (name "Net-(D3-A)") (class "Default")
      (node (ref "C4") (pin "1") (pinfunction "1_1") (pintype "passive"))
      (node (ref "D3") (pin "2") (pinfunction "A_2") (pintype "bidirectional"))
      (node (ref "D4") (pin "1") (pinfunction "K_1") (pintype "bidirectional"))
    )
    (net (code "24") (name "Net-(D7-CATHODE)") (class "Default")
      (node (ref "D7") (pin "1") (pinfunction "CATHODE_1") (pintype "bidirectional"))
      (node (ref "R_CAPACITOR") (pin "1") (pinfunction "1_1") (pintype "passive"))
    )
    (net (code "25") (name "Net-(EPD_C1-Pad1)") (class "Default")
      (node (ref "EPD_C1") (pin "1") (pinfunction "1_1") (pintype "passive"))
      (node (ref "J1") (pin "4") (pinfunction "4_4") (pintype "bidirectional"))
    )
    (net (code "26") (name "Net-(EPD_C2-Pad1)") (class "Default")
      (node (ref "EPD_C2") (pin "1") (pinfunction "1_1") (pintype "passive"))
      (node (ref "J1") (pin "5") (pinfunction "5_5") (pintype "bidirectional"))
    )
    (net (code "27") (name "Net-(EPD_C6-Pad1)") (class "Default")
      (node (ref "EPD_C6") (pin "1") (pinfunction "1_1") (pintype "passive"))
      (node (ref "J1") (pin "18") (pinfunction "18_18") (pintype "bidirectional"))
    )
    (net (code "28") (name "Net-(EPD_C7-Pad1)") (class "Default")
      (node (ref "EPD_C7") (pin "1") (pinfunction "1_1") (pintype "passive"))
      (node (ref "J1") (pin "19") (pinfunction "19_19") (pintype "bidirectional"))
    )
    (net (code "29") (name "Net-(EPD_C8-Pad1)") (class "Default")
      (node (ref "EPD_C8") (pin "1") (pinfunction "1_1") (pintype "passive"))
      (node (ref "J1") (pin "20") (pinfunction "20_20") (pintype "bidirectional"))
    )
    (net (code "30") (name "Net-(EPD_C10-Pad1)") (class "Default")
      (node (ref "EPD_C10") (pin "1") (pinfunction "1_1") (pintype "passive"))
      (node (ref "J1") (pin "22") (pinfunction "22_22") (pintype "bidirectional"))
    )
    (net (code "31") (name "Net-(EPD_C12-Pad1)") (class "Default")
      (node (ref "EPD_C12") (pin "1") (pinfunction "1_1") (pintype "passive"))
      (node (ref "J1") (pin "24") (pinfunction "24_24") (pintype "bidirectional"))
    )
    (net (code "32") (name "Net-(IC1-CT)") (class "Default")
      (node (ref "C_DELAY") (pin "1") (pinfunction "1_1") (pintype "passive"))
      (node (ref "IC1") (pin "5") (pinfunction "CT_5") (pintype "bidirectional"))
    )
    (net (code "33") (name "Net-(J2-PadA5)") (class "Default")
      (node (ref "J2") (pin "A5") (pinfunction "A5_A5") (pintype "bidirectional"))
      (node (ref "R2-USB1") (pin "2") (pinfunction "2_2") (pintype "passive"))
    )
    (net (code "34") (name "Net-(J2-PadB5)") (class "Default")
      (node (ref "J2") (pin "B5") (pinfunction "B5_B5") (pintype "bidirectional"))
      (node (ref "R2_USB") (pin "1") (pinfunction "1_1") (pintype "passive"))
    )
    (net (code "35") (name "Net-(MCP73831-PROG)") (class "Default")
      (node (ref "MCP73831") (pin "5") (pinfunction "PROG_5") (pintype "input"))
      (node (ref "R2_BAT") (pin "2") (pinfunction "2_2") (pintype "passive"))
    )
    (net (code "36") (name "Net-(MCP73831-STAT)") (class "Default")
      (node (ref "MCP73831") (pin "1") (pinfunction "STAT_1") (pintype "output"))
      (node (ref "R1_BAT") (pin "2") (pinfunction "2_2") (pintype "passive"))
    )
    (net (code "37") (name "PREVGH") (class "Default")
      (node (ref "D5") (pin "1") (pinfunction "K_1") (pintype "bidirectional"))
      (node (ref "EPD_C9") (pin "1") (pinfunction "1_1") (pintype "passive"))
      (node (ref "J1") (pin "21") (pinfunction "21_21") (pintype "bidirectional"))
    )
    (net (code "38") (name "PREVGL") (class "Default")
      (node (ref "D4") (pin "2") (pinfunction "A_2") (pintype "bidirectional"))
      (node (ref "EPD_C11") (pin "1") (pinfunction "1_1") (pintype "passive"))
      (node (ref "J1") (pin "23") (pinfunction "23_23") (pintype "bidirectional"))
    )
    (net (code "39") (name "RESE") (class "Default")
      (node (ref "J1") (pin "3") (pinfunction "3_3") (pintype "bidirectional"))
      (node (ref "Q3") (pin "2") (pinfunction "S_2") (pintype "bidirectional"))
      (node (ref "R3") (pin "2") (pinfunction "2_2") (pintype "passive"))
    )
    (net (code "40") (name "RESE'") (class "Default")
      (node (ref "R2") (pin "2") (pinfunction "2_2") (pintype "passive"))
      (node (ref "R3") (pin "1") (pinfunction "1_1") (pintype "passive"))
      (node (ref "SJ1") (pin "2") (pinfunction "2_2") (pintype "passive"))
    )
    (net (code "41") (name "RESET") (class "Default")
      (node (ref "C5") (pin "1") (pinfunction "1_1") (pintype "passive"))
      (node (ref "IC1") (pin "1") (pinfunction "VOUT_1") (pintype "bidirectional"))
      (node (ref "RESET_BUTTON") (pin "3") (pinfunction "3_3") (pintype "passive"))
      (node (ref "RESET_BUTTON") (pin "4") (pinfunction "4_4") (pintype "passive"))
      (node (ref "R_RESET") (pin "1") (pinfunction "1_1") (pintype "passive"))
      (node (ref "U2") (pin "3") (pinfunction "EN_3") (pintype "input"))
    )
    (net (code "42") (name "RTC_RST") (class "Default")
      (node (ref "U2") (pin "16") (pinfunction "IO18_16") (pintype "bidirectional"))
      (node (ref "U3") (pin "4") (pinfunction "~{RST}_4") (pintype "input"))
    )
    (net (code "43") (name "RX") (class "Default")
      (node (ref "TP2") (pin "TP") (pinfunction "TP_TP") (pintype "input"))
      (node (ref "U2") (pin "24") (pinfunction "RXD0/GPIO17_24") (pintype "bidirectional"))
    )
    (net (code "44") (name "SCK") (class "Default")
      (node (ref "D10") (pin "2") (pinfunction "2_2") (pintype "passive"))
      (node (ref "J1") (pin "13") (pinfunction "13_13") (pintype "bidirectional"))
      (node (ref "J4") (pin "P5") (pinfunction "CLK_P5") (pintype "bidirectional"))
      (node (ref "R6") (pin "1") (pinfunction "1_1") (pintype "passive"))
      (node (ref "TP8") (pin "TP") (pinfunction "TP_TP") (pintype "input"))
      (node (ref "U1") (pin "6") (pinfunction "CLK_6") (pintype "input"))
      (node (ref "U2") (pin "6") (pinfunction "IO6_6") (pintype "bidirectional"))
    )
    (net (code "45") (name "SCL") (class "Default")
      (node (ref "J3") (pin "4") (pinfunction "4_4") (pintype "passive"))
      (node (ref "R2_PINH") (pin "1") (pinfunction "1_1") (pintype "passive"))
      (node (ref "SENSOR2") (pin "4") (pinfunction "SCK_4") (pintype "input"))
      (node (ref "U2") (pin "20") (pinfunction "IO22_20") (pintype "bidirectional"))
      (node (ref "U3") (pin "16") (pinfunction "SCL_16") (pintype "input"))
      (node (ref "U4") (pin "7") (pinfunction "SCL_7") (pintype "input"))
    )
    (net (code "46") (name "SDA") (class "Default")
      (node (ref "J3") (pin "3") (pinfunction "3_3") (pintype "passive"))
      (node (ref "R1_PINH") (pin "1") (pinfunction "1_1") (pintype "passive"))
      (node (ref "SENSOR2") (pin "3") (pinfunction "SDI_3") (pintype "bidirectional"))
      (node (ref "U2") (pin "19") (pinfunction "IO21_19") (pintype "bidirectional"))
      (node (ref "U3") (pin "15") (pinfunction "SDA_15") (pintype "bidirectional"))
      (node (ref "U4") (pin "8") (pinfunction "SDA_8") (pintype "bidirectional"))
    )
    (net (code "47") (name "SRC") (class "Default")
      (node (ref "C4") (pin "2") (pinfunction "2_2") (pintype "passive"))
      (node (ref "D5") (pin "2") (pinfunction "A_2") (pintype "bidirectional"))
      (node (ref "L1") (pin "1") (pinfunction "1_1") (pintype "passive"))
      (node (ref "Q3") (pin "3") (pinfunction "D_3") (pintype "bidirectional"))
    )
    (net (code "48") (name "SS_SD") (class "Default")
      (node (ref "D8") (pin "2") (pinfunction "2_2") (pintype "passive"))
      (node (ref "J4") (pin "P2") (pinfunction "CD/DAT3_P2") (pintype "bidirectional"))
      (node (ref "R10") (pin "1") (pinfunction "1_1") (pintype "passive"))
      (node (ref "U2") (pin "4") (pinfunction "IO4_4") (pintype "bidirectional"))
    )
    (net (code "49") (name "TX") (class "Default")
      (node (ref "TP1") (pin "TP") (pinfunction "TP_TP") (pintype "input"))
      (node (ref "U2") (pin "25") (pinfunction "TXD0/GPIO16_25") (pintype "bidirectional"))
    )
    (net (code "50") (name "USB_D+") (class "Default")
      (node (ref "D1") (pin "1") (pinfunction "I/O1_1_1") (pintype "bidirectional"))
      (node (ref "U2") (pin "14") (pinfunction "IO13_14") (pintype "bidirectional"))
    )
    (net (code "51") (name "USB_D-") (class "Default")
      (node (ref "D1") (pin "3") (pinfunction "I/O2_1_3") (pintype "bidirectional"))
      (node (ref "U2") (pin "13") (pinfunction "IO12_13") (pintype "bidirectional"))
    )
    (net (code "52") (name "VBAT") (class "Default")
      (node (ref "C2_BAT") (pin "1") (pinfunction "1_1") (pintype "passive"))
      (node (ref "MCP73831") (pin "3") (pinfunction "VBAT_3") (pintype "power_in"))
      (node (ref "Q1") (pin "3") (pinfunction "D_3") (pintype "bidirectional"))
      (node (ref "TP3") (pin "TP") (pinfunction "TP_TP") (pintype "input"))
      (node (ref "U4") (pin "2") (pinfunction "CELL_2") (pintype "power_in"))
      (node (ref "U4") (pin "3") (pinfunction "VDD_3") (pintype "power_in"))
    )
    (net (code "53") (name "VBUS") (class "Default")
      (node (ref "C1_BAT") (pin "1") (pinfunction "1_1") (pintype "passive"))
      (node (ref "C4_USB") (pin "1") (pinfunction "1_1") (pintype "passive"))
      (node (ref "C5_USB") (pin "1") (pinfunction "1_1") (pintype "passive"))
      (node (ref "CHG_LED") (pin "A") (pinfunction "A_A") (pintype "passive"))
      (node (ref "D1") (pin "5") (pinfunction "VBUS_5") (pintype "bidirectional"))
      (node (ref "D2") (pin "2") (pinfunction "ANODE_2") (pintype "bidirectional"))
      (node (ref "MCP73831") (pin "4") (pinfunction "VIN_4") (pintype "power_in"))
      (node (ref "PFMF.050.1") (pin "2") (pinfunction "2_2") (pintype "passive"))
      (node (ref "Q1") (pin "1") (pinfunction "G_1") (pintype "bidirectional"))
      (node (ref "R1_PWRUSB") (pin "2") (pinfunction "2_2") (pintype "passive"))
      (node (ref "TP14") (pin "TP") (pinfunction "TP_TP") (pintype "input"))
    )
    (net (code "54") (name "VRTC") (class "Default")
      (node (ref "C10_SUPERCAP") (pin "2") (pinfunction "2_2") (pintype "passive"))
      (node (ref "C8") (pin "1") (pinfunction "1_1") (pintype "passive"))
      (node (ref "R_CAPACITOR") (pin "2") (pinfunction "2_2") (pintype "passive"))
      (node (ref "U3") (pin "14") (pinfunction "VBAT_14") (pintype "power_in"))
    )
    (net (code "55") (name "VUSB") (class "Default")
      (node (ref "J2") (pin "A4") (pinfunction "A4_A4") (pintype "bidirectional"))
      (node (ref "J2") (pin "A9") (pinfunction "A9_A9") (pintype "bidirectional"))
      (node (ref "J2") (pin "B4") (pinfunction "B4_B4") (pintype "bidirectional"))
      (node (ref "J2") (pin "B9") (pinfunction "B9_B9") (pintype "bidirectional"))
      (node (ref "PFMF.050.1") (pin "1") (pinfunction "1_1") (pintype "passive"))
    )
    (net (code "56") (name "unconnected-(IC1-NC-Pad4)") (class "Default")
      (node (ref "IC1") (pin "4") (pinfunction "NC_4") (pintype "no_connect"))
    )
    (net (code "57") (name "unconnected-(IC4-NC-Pad4)") (class "Default")
      (node (ref "IC4") (pin "4") (pinfunction "NC_4") (pintype "no_connect"))
    )
    (net (code "58") (name "unconnected-(J1-Pad1)") (class "Default")
      (node (ref "J1") (pin "1") (pinfunction "1_1") (pintype "bidirectional"))
    )
    (net (code "59") (name "unconnected-(J1-Pad6)") (class "Default")
      (node (ref "J1") (pin "6") (pinfunction "6_6") (pintype "bidirectional"))
    )
    (net (code "60") (name "unconnected-(J1-Pad7)") (class "Default")
      (node (ref "J1") (pin "7") (pinfunction "7_7") (pintype "bidirectional"))
    )
    (net (code "61") (name "unconnected-(J2-PadA8)") (class "Default")
      (node (ref "J2") (pin "A8") (pinfunction "A8_A8") (pintype "bidirectional"))
    )
    (net (code "62") (name "unconnected-(J2-PadB8)") (class "Default")
      (node (ref "J2") (pin "B8") (pinfunction "B8_B8") (pintype "bidirectional"))
    )
    (net (code "63") (name "unconnected-(J4-DAT1-PadP8)") (class "Default")
      (node (ref "J4") (pin "P8") (pinfunction "DAT1_P8") (pintype "bidirectional"))
    )
    (net (code "64") (name "unconnected-(J4-DAT2-PadP1)") (class "Default")
      (node (ref "J4") (pin "P1") (pinfunction "DAT2_P1") (pintype "bidirectional"))
    )
    (net (code "65") (name "unconnected-(J4-DETECTION_1-PadS1)") (class "Default")
      (node (ref "J4") (pin "S1") (pinfunction "DETECTION_1_S1") (pintype "bidirectional"))
    )
    (net (code "66") (name "unconnected-(J4-DETECTION_2-PadS2)") (class "Default")
      (node (ref "J4") (pin "S2") (pinfunction "DETECTION_2_S2") (pintype "bidirectional"))
    )
    (net (code "67") (name "unconnected-(U2-NC-Pad22)") (class "Default")
      (node (ref "U2") (pin "22") (pinfunction "NC_22") (pintype "no_connect"))
    )
    (net (code "68") (name "unconnected-(U4-~{ALERT}-Pad5)") (class "Default")
      (node (ref "U4") (pin "5") (pinfunction "~{ALERT}_5") (pintype "output"))
    )
  )
)
